# deepshark_ecs.net
KiCad netlist of a schematic drawn in Altium Designer
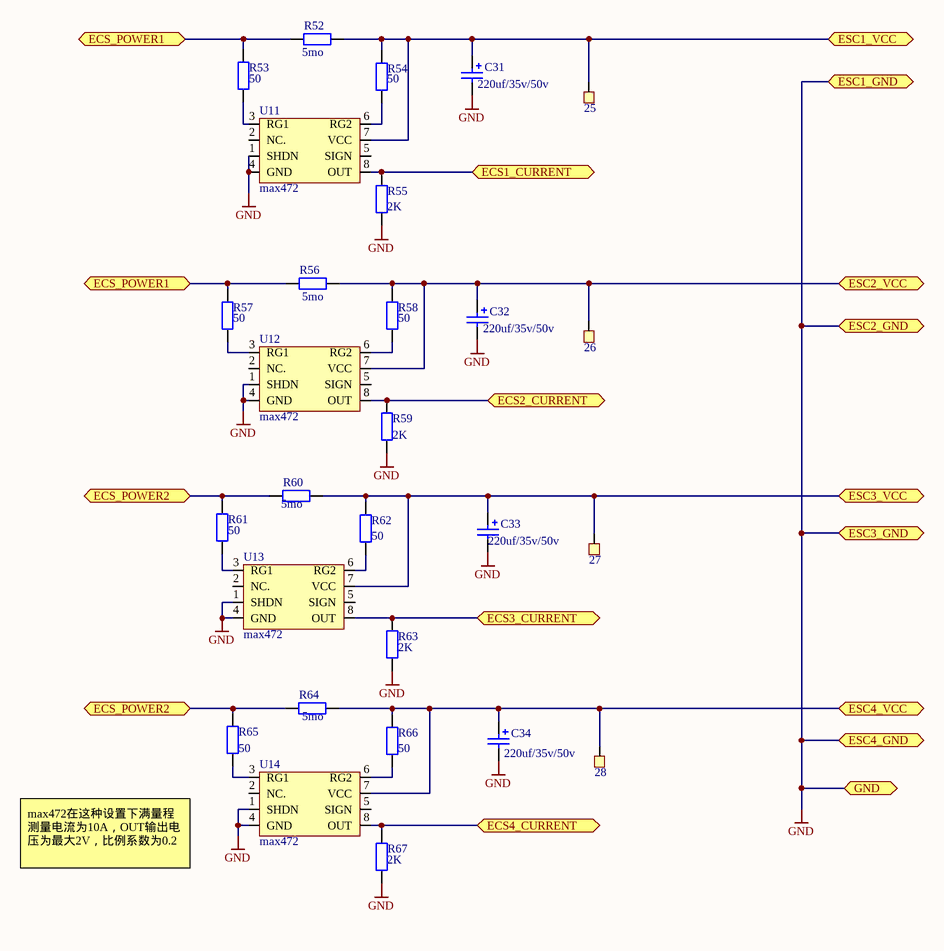
[diagram p0: deepshark_ecs.SchDoc]

(export (version "E")
  (design (tool "Eeschema 10.0.6"))
  (components
    (comp (ref "25") (value "TP") (footprint "TestPoint") (libsource (lib "deepshark_sch_lib") (part "TP")))
    (comp (ref "26") (value "TP") (footprint "TestPoint") (libsource (lib "deepshark_sch_lib") (part "TP")))
    (comp (ref "27") (value "TP") (footprint "TestPoint") (libsource (lib "deepshark_sch_lib") (part "TP")))
    (comp (ref "28") (value "TP") (footprint "TestPoint") (libsource (lib "deepshark_sch_lib") (part "TP")))
    (comp (ref "C31")
      (value "220uf/35v/50v")
      (footprint "220uf-50v")
      (description "Polarized Capacitor (Axial)")
      (fields (field (name "Comment") "Cap Pol2") (field (name "PUBLISHER") "Altium Limited"))
      (libsource (lib "Miscellaneous Devices") (part "Cap Pol2"))
    )
    (comp (ref "C32")
      (value "220uf/35v/50v")
      (footprint "220uf-50v")
      (description "Polarized Capacitor (Axial)")
      (fields (field (name "Comment") "Cap Pol2") (field (name "PUBLISHER") "Altium Limited"))
      (libsource (lib "Miscellaneous Devices") (part "Cap Pol2"))
    )
    (comp (ref "C33")
      (value "220uf/35v/50v")
      (footprint "220uf-50v")
      (description "Polarized Capacitor (Axial)")
      (fields (field (name "Comment") "Cap Pol2") (field (name "PUBLISHER") "Altium Limited"))
      (libsource (lib "Miscellaneous Devices") (part "Cap Pol2"))
    )
    (comp (ref "C34")
      (value "220uf/35v/50v")
      (footprint "220uf-50v")
      (description "Polarized Capacitor (Axial)")
      (fields (field (name "Comment") "Cap Pol2") (field (name "PUBLISHER") "Altium Limited"))
      (libsource (lib "Miscellaneous Devices") (part "Cap Pol2"))
    )
    (comp (ref "R52")
      (value "5mo")
      (footprint "5mo")
      (description "Resistor")
      (fields (field (name "Comment") "Res2") (field (name "PUBLISHER") "Altium Limited"))
      (libsource (lib "") (part "Res2_1"))
    )
    (comp (ref "R53")
      (value "50")
      (footprint "my0603")
      (description "Resistor")
      (fields (field (name "Comment") "Res2") (field (name "PUBLISHER") "Altium Limited"))
      (libsource (lib "Miscellaneous Devices") (part "Res2"))
    )
    (comp (ref "R54")
      (value "50")
      (footprint "my0603")
      (description "Resistor")
      (fields (field (name "Comment") "Res2") (field (name "PUBLISHER") "Altium Limited"))
      (libsource (lib "Miscellaneous Devices") (part "Res2"))
    )
    (comp (ref "R55")
      (value "2K")
      (footprint "6-0805_M")
      (description "Resistor")
      (fields (field (name "Comment") "Res2") (field (name "PUBLISHER") "Altium Limited"))
      (libsource (lib "Miscellaneous Devices") (part "Res2"))
    )
    (comp (ref "R56")
      (value "5mo")
      (footprint "5mo")
      (description "Resistor")
      (fields (field (name "Comment") "Res2") (field (name "PUBLISHER") "Altium Limited"))
      (libsource (lib "") (part "Res2_1"))
    )
    (comp (ref "R57")
      (value "50")
      (footprint "my0603")
      (description "Resistor")
      (fields (field (name "Comment") "Res2") (field (name "PUBLISHER") "Altium Limited"))
      (libsource (lib "Miscellaneous Devices") (part "Res2"))
    )
    (comp (ref "R58")
      (value "50")
      (footprint "my0603")
      (description "Resistor")
      (fields (field (name "Comment") "Res2") (field (name "PUBLISHER") "Altium Limited"))
      (libsource (lib "Miscellaneous Devices") (part "Res2"))
    )
    (comp (ref "R59")
      (value "2K")
      (footprint "6-0805_M")
      (description "Resistor")
      (fields (field (name "Comment") "Res2") (field (name "PUBLISHER") "Altium Limited"))
      (libsource (lib "Miscellaneous Devices") (part "Res2"))
    )
    (comp (ref "R60")
      (value "5mo")
      (footprint "5mo")
      (description "Resistor")
      (fields (field (name "Comment") "Res2") (field (name "PUBLISHER") "Altium Limited"))
      (libsource (lib "") (part "Res2_1"))
    )
    (comp (ref "R61")
      (value "50")
      (footprint "my0603")
      (description "Resistor")
      (fields (field (name "Comment") "Res2") (field (name "PUBLISHER") "Altium Limited"))
      (libsource (lib "Miscellaneous Devices") (part "Res2"))
    )
    (comp (ref "R62")
      (value "50")
      (footprint "my0603")
      (description "Resistor")
      (fields (field (name "Comment") "Res2") (field (name "PUBLISHER") "Altium Limited"))
      (libsource (lib "Miscellaneous Devices") (part "Res2"))
    )
    (comp (ref "R63")
      (value "2K")
      (footprint "6-0805_M")
      (description "Resistor")
      (fields (field (name "Comment") "Res2") (field (name "PUBLISHER") "Altium Limited"))
      (libsource (lib "Miscellaneous Devices") (part "Res2"))
    )
    (comp (ref "R64")
      (value "5mo")
      (footprint "5mo")
      (description "Resistor")
      (fields (field (name "Comment") "Res2") (field (name "PUBLISHER") "Altium Limited"))
      (libsource (lib "") (part "Res2_1"))
    )
    (comp (ref "R65")
      (value "50")
      (footprint "my0603")
      (description "Resistor")
      (fields (field (name "Comment") "Res2") (field (name "PUBLISHER") "Altium Limited"))
      (libsource (lib "Miscellaneous Devices") (part "Res2"))
    )
    (comp (ref "R66")
      (value "50")
      (footprint "my0603")
      (description "Resistor")
      (fields (field (name "Comment") "Res2") (field (name "PUBLISHER") "Altium Limited"))
      (libsource (lib "Miscellaneous Devices") (part "Res2"))
    )
    (comp (ref "R67")
      (value "2K")
      (footprint "6-0805_M")
      (description "Resistor")
      (fields (field (name "Comment") "Res2") (field (name "PUBLISHER") "Altium Limited"))
      (libsource (lib "Miscellaneous Devices") (part "Res2"))
    )
    (comp (ref "U11")
      (value "max472")
      (footprint "SO-8_M")
      (libsource (lib "deepshark_sch_lib") (part "max472"))
    )
    (comp (ref "U12")
      (value "max472")
      (footprint "SO-8_M")
      (libsource (lib "deepshark_sch_lib") (part "max472"))
    )
    (comp (ref "U13")
      (value "max472")
      (footprint "SO-8_M")
      (libsource (lib "deepshark_sch_lib") (part "max472"))
    )
    (comp (ref "U14")
      (value "max472")
      (footprint "SO-8_M")
      (libsource (lib "deepshark_sch_lib") (part "max472"))
    )
  )
  (nets
    (net (code "1") (name "/ECS1_CURRENT") (class "Default")
      (node (ref "R55") (pin "2") (pinfunction "2_2") (pintype "passive"))
      (node (ref "U11") (pin "8") (pinfunction "OUT_8") (pintype "passive"))
    )
    (net (code "2") (name "/ECS2_CURRENT") (class "Default")
      (node (ref "R59") (pin "2") (pinfunction "2_2") (pintype "passive"))
      (node (ref "U12") (pin "8") (pinfunction "OUT_8") (pintype "passive"))
    )
    (net (code "3") (name "/ECS3_CURRENT") (class "Default")
      (node (ref "R63") (pin "2") (pinfunction "2_2") (pintype "passive"))
      (node (ref "U13") (pin "8") (pinfunction "OUT_8") (pintype "passive"))
    )
    (net (code "4") (name "/ECS4_CURRENT") (class "Default")
      (node (ref "R67") (pin "2") (pinfunction "2_2") (pintype "passive"))
      (node (ref "U14") (pin "8") (pinfunction "OUT_8") (pintype "passive"))
    )
    (net (code "5") (name "/ECS_POWER1") (class "Default")
      (node (ref "R52") (pin "1") (pinfunction "1_1") (pintype "passive"))
      (node (ref "R53") (pin "2") (pinfunction "2_2") (pintype "passive"))
      (node (ref "R56") (pin "1") (pinfunction "1_1") (pintype "passive"))
      (node (ref "R57") (pin "2") (pinfunction "2_2") (pintype "passive"))
    )
    (net (code "6") (name "/ECS_POWER2") (class "Default")
      (node (ref "R60") (pin "1") (pinfunction "1_1") (pintype "passive"))
      (node (ref "R61") (pin "2") (pinfunction "2_2") (pintype "passive"))
      (node (ref "R64") (pin "1") (pinfunction "1_1") (pintype "passive"))
      (node (ref "R65") (pin "2") (pinfunction "2_2") (pintype "passive"))
    )
    (net (code "7") (name "/ESC1_VCC") (class "Default")
      (node (ref "25") (pin "1") (pinfunction "1_1") (pintype "passive"))
      (node (ref "C31") (pin "1") (pinfunction "1_1") (pintype "passive"))
      (node (ref "R52") (pin "2") (pinfunction "2_2") (pintype "passive"))
      (node (ref "R54") (pin "2") (pinfunction "2_2") (pintype "passive"))
      (node (ref "U11") (pin "7") (pinfunction "VCC_7") (pintype "passive"))
    )
    (net (code "8") (name "/ESC2_VCC") (class "Default")
      (node (ref "26") (pin "1") (pinfunction "1_1") (pintype "passive"))
      (node (ref "C32") (pin "1") (pinfunction "1_1") (pintype "passive"))
      (node (ref "R56") (pin "2") (pinfunction "2_2") (pintype "passive"))
      (node (ref "R58") (pin "2") (pinfunction "2_2") (pintype "passive"))
      (node (ref "U12") (pin "7") (pinfunction "VCC_7") (pintype "passive"))
    )
    (net (code "9") (name "/ESC3_VCC") (class "Default")
      (node (ref "27") (pin "1") (pinfunction "1_1") (pintype "passive"))
      (node (ref "C33") (pin "1") (pinfunction "1_1") (pintype "passive"))
      (node (ref "R60") (pin "2") (pinfunction "2_2") (pintype "passive"))
      (node (ref "R62") (pin "2") (pinfunction "2_2") (pintype "passive"))
      (node (ref "U13") (pin "7") (pinfunction "VCC_7") (pintype "passive"))
    )
    (net (code "10") (name "/ESC4_VCC") (class "Default")
      (node (ref "28") (pin "1") (pinfunction "1_1") (pintype "passive"))
      (node (ref "C34") (pin "1") (pinfunction "1_1") (pintype "passive"))
      (node (ref "R64") (pin "2") (pinfunction "2_2") (pintype "passive"))
      (node (ref "R66") (pin "2") (pinfunction "2_2") (pintype "passive"))
      (node (ref "U14") (pin "7") (pinfunction "VCC_7") (pintype "passive"))
    )
    (net (code "11") (name "GND") (class "Default")
      (node (ref "C31") (pin "2") (pinfunction "2_2") (pintype "passive"))
      (node (ref "C32") (pin "2") (pinfunction "2_2") (pintype "passive"))
      (node (ref "C33") (pin "2") (pinfunction "2_2") (pintype "passive"))
      (node (ref "C34") (pin "2") (pinfunction "2_2") (pintype "passive"))
      (node (ref "R55") (pin "1") (pinfunction "1_1") (pintype "passive"))
      (node (ref "R59") (pin "1") (pinfunction "1_1") (pintype "passive"))
      (node (ref "R63") (pin "1") (pinfunction "1_1") (pintype "passive"))
      (node (ref "R67") (pin "1") (pinfunction "1_1") (pintype "passive"))
      (node (ref "U11") (pin "1") (pinfunction "SHDN_1") (pintype "passive"))
      (node (ref "U11") (pin "4") (pinfunction "GND_4") (pintype "passive"))
      (node (ref "U12") (pin "1") (pinfunction "SHDN_1") (pintype "passive"))
      (node (ref "U12") (pin "4") (pinfunction "GND_4") (pintype "passive"))
      (node (ref "U13") (pin "1") (pinfunction "SHDN_1") (pintype "passive"))
      (node (ref "U13") (pin "4") (pinfunction "GND_4") (pintype "passive"))
      (node (ref "U14") (pin "1") (pinfunction "SHDN_1") (pintype "passive"))
      (node (ref "U14") (pin "4") (pinfunction "GND_4") (pintype "passive"))
    )
    (net (code "12") (name "Net-(U11-RG1)") (class "Default")
      (node (ref "R53") (pin "1") (pinfunction "1_1") (pintype "passive"))
      (node (ref "U11") (pin "3") (pinfunction "RG1_3") (pintype "passive"))
    )
    (net (code "13") (name "Net-(U11-RG2)") (class "Default")
      (node (ref "R54") (pin "1") (pinfunction "1_1") (pintype "passive"))
      (node (ref "U11") (pin "6") (pinfunction "RG2_6") (pintype "passive"))
    )
    (net (code "14") (name "Net-(U12-RG1)") (class "Default")
      (node (ref "R57") (pin "1") (pinfunction "1_1") (pintype "passive"))
      (node (ref "U12") (pin "3") (pinfunction "RG1_3") (pintype "passive"))
    )
    (net (code "15") (name "Net-(U12-RG2)") (class "Default")
      (node (ref "R58") (pin "1") (pinfunction "1_1") (pintype "passive"))
      (node (ref "U12") (pin "6") (pinfunction "RG2_6") (pintype "passive"))
    )
    (net (code "16") (name "Net-(U13-RG1)") (class "Default")
      (node (ref "R61") (pin "1") (pinfunction "1_1") (pintype "passive"))
      (node (ref "U13") (pin "3") (pinfunction "RG1_3") (pintype "passive"))
    )
    (net (code "17") (name "Net-(U13-RG2)") (class "Default")
      (node (ref "R62") (pin "1") (pinfunction "1_1") (pintype "passive"))
      (node (ref "U13") (pin "6") (pinfunction "RG2_6") (pintype "passive"))
    )
    (net (code "18") (name "Net-(U14-RG1)") (class "Default")
      (node (ref "R65") (pin "1") (pinfunction "1_1") (pintype "passive"))
      (node (ref "U14") (pin "3") (pinfunction "RG1_3") (pintype "passive"))
    )
    (net (code "19") (name "Net-(U14-RG2)") (class "Default")
      (node (ref "R66") (pin "1") (pinfunction "1_1") (pintype "passive"))
      (node (ref "U14") (pin "6") (pinfunction "RG2_6") (pintype "passive"))
    )
    (net (code "20") (name "unconnected-(U11-NC.-Pad2)") (class "Default")
      (node (ref "U11") (pin "2") (pinfunction "NC._2") (pintype "passive"))
    )
    (net (code "21") (name "unconnected-(U11-SIGN-Pad5)") (class "Default")
      (node (ref "U11") (pin "5") (pinfunction "SIGN_5") (pintype "passive"))
    )
    (net (code "22") (name "unconnected-(U12-NC.-Pad2)") (class "Default")
      (node (ref "U12") (pin "2") (pinfunction "NC._2") (pintype "passive"))
    )
    (net (code "23") (name "unconnected-(U12-SIGN-Pad5)") (class "Default")
      (node (ref "U12") (pin "5") (pinfunction "SIGN_5") (pintype "passive"))
    )
    (net (code "24") (name "unconnected-(U13-NC.-Pad2)") (class "Default")
      (node (ref "U13") (pin "2") (pinfunction "NC._2") (pintype "passive"))
    )
    (net (code "25") (name "unconnected-(U13-SIGN-Pad5)") (class "Default")
      (node (ref "U13") (pin "5") (pinfunction "SIGN_5") (pintype "passive"))
    )
    (net (code "26") (name "unconnected-(U14-NC.-Pad2)") (class "Default")
      (node (ref "U14") (pin "2") (pinfunction "NC._2") (pintype "passive"))
    )
    (net (code "27") (name "unconnected-(U14-SIGN-Pad5)") (class "Default")
      (node (ref "U14") (pin "5") (pinfunction "SIGN_5") (pintype "passive"))
    )
  )
)
